# Power.net
KiCad netlist of a schematic drawn in Altium Designer
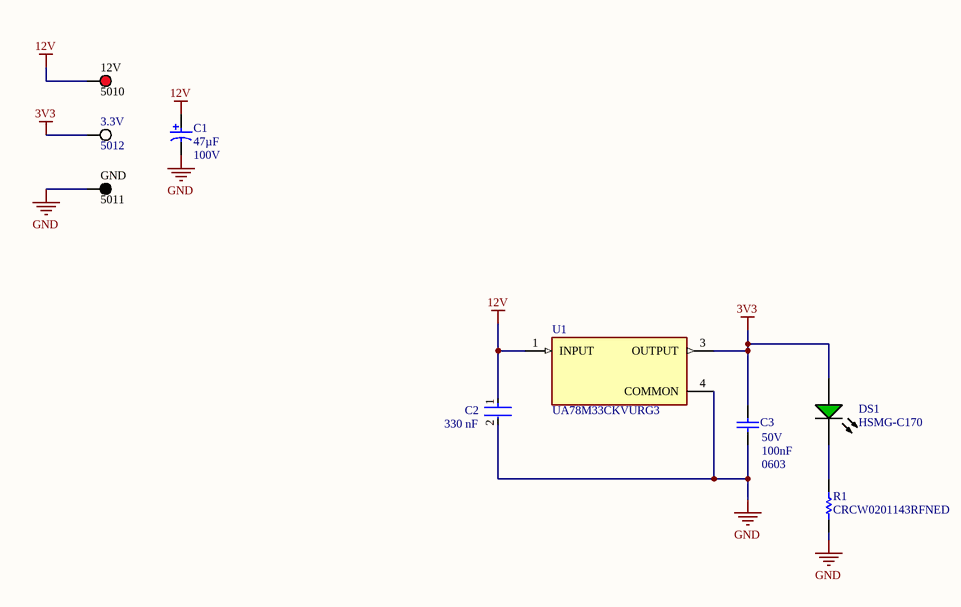
[diagram p0: Power.SchDoc]

(export (version "E")
  (design (tool "Eeschema 10.0.6"))
  (components
    (comp (ref "3.3V")
      (value "5012")
      (footprint "KSTN-5012_V")
      (description "Test Point, White, Through Hole, RoHS, Bulk")
      (fields (field (name "MANUFACTURER") "Keystone"))
      (libsource (lib "Altium Content Vault") (part "TESTPOINT_WHITE"))
    )
    (comp (ref "12V")
      (value "5010")
      (footprint "KSTN-5010_V")
      (description "Test Point, Red, Through Hole, RoHS, Bulk")
      (fields (field (name "MANUFACTURER") "Keystone"))
      (libsource (lib "Altium Content Vault") (part "TESTPOINT_RED"))
    )
    (comp (ref "C1")
      (value "UUX2A470MNL1GS")
      (footprint "NIC-UUX2A470MNL1GS_L")
      (fields
        (field (name "MANUFACTURER") "Nichicon")
        (field (name "CAPACITANCE") "47µF")
        (field (name "TOLERANCE") "20%")
        (field (name "VOLTAGE") "100V")
      )
      (libsource (lib "Altium Content Vault") (part "CAP-P-2"))
    )
    (comp (ref "C2")
      (value "330 nF")
      (footprint "FP-CC0805-0_85-MFG")
      (description "Surface Mount Ceramic Multilayer Capacitor 0.33uF 10% X7R 16V 0805 Blister T/R")
      (fields (field (name "MANUFACTURER PART NUMBER") "CC0805KKX7R7BB334") (field (name "TOLERANCE") "0.1"))
      (libsource (lib "Altium Content Vault") (part "11868f565c42a9108669ba33697ecf6"))
    )
    (comp (ref "C3")
      (value "C0603X104K5RACTU")
      (footprint "CAPC1608X87X35NL15T15")
      (fields
        (field (name "MANUFACTURER") "Kemet")
        (field (name "CASE CODE (IMPERIAL)") "0603")
        (field (name "CAPACITANCE") "100nF")
        (field (name "TOLERANCE") "10%")
        (field (name "VOLTAGE") "50V")
      )
      (libsource (lib "Altium Content Vault") (part "CAP"))
    )
    (comp (ref "DS1")
      (value "HSMG-C170")
      (footprint "AVAG-HSMX-C170_V")
      (description "Chip LED, Green, 2.2 V, -40 to 85 degC, 2-Pin SMD, Pb-Free, Tape and Reel")
      (fields (field (name "MANUFACTURER") "Avago"))
      (libsource (lib "Altium Content Vault") (part "LED_GREEN_A1K2-2"))
    )
    (comp (ref "GND")
      (value "5011")
      (footprint "KSTN-5011_V")
      (description "Test Point, Black, Through Hole, RoHS, Bulk")
      (fields (field (name "MANUFACTURER") "Keystone"))
      (libsource (lib "Altium Content Vault") (part "TESTPOINT_BLACK"))
    )
    (comp (ref "R1")
      (value "CRCW0201143RFNED")
      (footprint "RESC0603X28X15ML05T05")
      (fields (field (name "MANUFACTURER") "Vishay Dale"))
      (libsource (lib "Altium Content Vault") (part "RES"))
    )
    (comp (ref "U1")
      (value "UA78M33CKVURG3")
      (footprint "FP-KVU0003A-MFG")
      (description "IC REG LINEAR 3.3V 500MA TO252-3")
      (fields
        (field (name "OCTOPART") "https://octopart.com/ua78m33ckvurg3-texas+instruments-669262")
        (field (name "MANUFACTURER") "Texas Instruments")
      )
      (libsource (lib "Altium Content Vault") (part "dd3c83ac2e246cf9e0dcbcc19b382eb"))
    )
  )
  (nets
    (net (code "1") (name "3V3") (class "Default")
      (node (ref "3.3V") (pin "1") (pinfunction "1_1") (pintype "passive"))
      (node (ref "C3") (pin "2") (pinfunction "2_2") (pintype "passive"))
      (node (ref "DS1") (pin "1") (pinfunction "A_1") (pintype "passive"))
      (node (ref "U1") (pin "3") (pinfunction "OUTPUT_3") (pintype "output"))
    )
    (net (code "2") (name "12V") (class "Default")
      (node (ref "12V") (pin "1") (pinfunction "1_1") (pintype "passive"))
      (node (ref "C1") (pin "1") (pinfunction "1_1") (pintype "passive"))
      (node (ref "C2") (pin "1") (pinfunction "1_1") (pintype "passive"))
      (node (ref "U1") (pin "1") (pinfunction "INPUT_1") (pintype "input"))
    )
    (net (code "3") (name "GND") (class "Default")
      (node (ref "C1") (pin "2") (pinfunction "2_2") (pintype "passive"))
      (node (ref "C2") (pin "2") (pinfunction "2_2") (pintype "passive"))
      (node (ref "C3") (pin "1") (pinfunction "1_1") (pintype "passive"))
      (node (ref "GND") (pin "1") (pinfunction "1_1") (pintype "passive"))
      (node (ref "R1") (pin "1") (pinfunction "1_1") (pintype "passive"))
      (node (ref "U1") (pin "4") (pinfunction "COMMON_4") (pintype "passive"))
    )
    (net (code "4") (name "Net-(DS1-K)") (class "Default")
      (node (ref "DS1") (pin "2") (pinfunction "K_2") (pintype "passive"))
      (node (ref "R1") (pin "2") (pinfunction "2_2") (pintype "passive"))
    )
  )
)
